# bandmodule.net
KiCad netlist of a schematic drawn in EAGLE
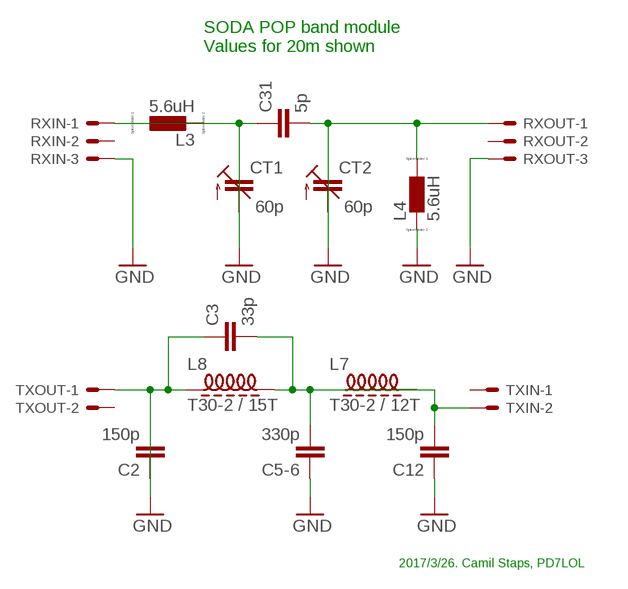
[diagram p0: schematic, sheet 1]

(export (version "E")
  (design (tool "Eeschema 10.0.6"))
  (components
    (comp (ref "C2")
      (value "150p")
      (footprint "eagle-import:C5B2.5")
      (libsource (lib "eagle-import") (part "C5/2.5"))
    )
    (comp (ref "C3")
      (value "33p")
      (footprint "eagle-import:C5B2.5")
      (libsource (lib "eagle-import") (part "C5/2.5"))
    )
    (comp (ref "C5-6")
      (value "330p")
      (footprint "eagle-import:C5B2.5")
      (libsource (lib "eagle-import") (part "C5/2.5"))
    )
    (comp (ref "C12")
      (value "150p")
      (footprint "eagle-import:C5B2.5")
      (libsource (lib "eagle-import") (part "C5/2.5"))
    )
    (comp (ref "C31")
      (value "5p")
      (footprint "eagle-import:C5B2.5")
      (libsource (lib "eagle-import") (part "C5/2.5"))
    )
    (comp (ref "CT1")
      (value "60p")
      (footprint "eagle-import:CTRIMTZ03")
      (libsource (lib "eagle-import") (part "C-TRIMMTZ03"))
    )
    (comp (ref "CT2")
      (value "60p")
      (footprint "eagle-import:CTRIMTZ03")
      (libsource (lib "eagle-import") (part "C-TRIMMTZ03"))
    )
    (comp (ref "L3")
      (value "5.6uH")
      (footprint "eagle-import:0207_10")
      (libsource (lib "eagle-import") (part "L0207/10"))
    )
    (comp (ref "L4")
      (value "5.6uH")
      (footprint "eagle-import:0207_10")
      (libsource (lib "eagle-import") (part "L0207/10"))
    )
    (comp (ref "L7")
      (value "T30-2 / 12T")
      (footprint "eagle-import:T30-2-28AWG-12T")
      (libsource (lib "eagle-import") (part "INDUCTORT30-2-28AWG-12T"))
    )
    (comp (ref "L8")
      (value "T30-2 / 15T")
      (footprint "eagle-import:T30-2-28AWG-12T")
      (libsource (lib "eagle-import") (part "INDUCTORT30-2-28AWG-12T"))
    )
    (comp (ref "RXIN")
      (value "22-23-2031")
      (footprint "eagle-import:22-23-2031")
      (fields (field (name "MF") "MOLEX"))
      (libsource (lib "eagle-import") (part "22-23-2031"))
    )
    (comp (ref "RXOUT")
      (value "22-23-2031")
      (footprint "eagle-import:22-23-2031")
      (fields (field (name "MF") "MOLEX"))
      (libsource (lib "eagle-import") (part "22-23-2031"))
    )
    (comp (ref "TXIN")
      (value "22-23-2021")
      (footprint "eagle-import:22-23-2021")
      (fields (field (name "MF") "MOLEX"))
      (libsource (lib "eagle-import") (part "22-23-2021"))
    )
    (comp (ref "TXOUT")
      (value "22-23-2021")
      (footprint "eagle-import:22-23-2021")
      (fields (field (name "MF") "MOLEX"))
      (libsource (lib "eagle-import") (part "22-23-2021"))
    )
  )
  (nets
    (net (code "1") (name "GND") (class "Default")
      (node (ref "C12") (pin "1") (pinfunction "1_1") (pintype "passive"))
      (node (ref "C2") (pin "2") (pinfunction "2_2") (pintype "passive"))
      (node (ref "C5-6") (pin "1") (pinfunction "1_1") (pintype "passive"))
      (node (ref "CT1") (pin "1") (pinfunction "E_1") (pintype "passive"))
      (node (ref "CT2") (pin "1") (pinfunction "E_1") (pintype "passive"))
      (node (ref "L4") (pin "2") (pinfunction "2_2") (pintype "passive"))
      (node (ref "RXIN") (pin "3") (pinfunction "S_3") (pintype "passive"))
      (node (ref "RXOUT") (pin "3") (pinfunction "S_3") (pintype "passive"))
    )
    (net (code "2") (name "Net-(CT1-A)") (class "Default")
      (node (ref "C31") (pin "1") (pinfunction "1_1") (pintype "passive"))
      (node (ref "CT1") (pin "2") (pinfunction "A_2") (pintype "passive"))
      (node (ref "L3") (pin "1") (pinfunction "1_1") (pintype "passive"))
    )
    (net (code "3") (name "Net-(CT2-A)") (class "Default")
      (node (ref "C31") (pin "2") (pinfunction "2_2") (pintype "passive"))
      (node (ref "CT2") (pin "2") (pinfunction "A_2") (pintype "passive"))
      (node (ref "L4") (pin "1") (pinfunction "1_1") (pintype "passive"))
      (node (ref "RXOUT") (pin "1") (pinfunction "S_1") (pintype "passive"))
    )
    (net (code "4") (name "Net-(L7-1)") (class "Default")
      (node (ref "C12") (pin "2") (pinfunction "2_2") (pintype "passive"))
      (node (ref "L7") (pin "P$1") (pinfunction "1_P$1") (pintype "passive"))
      (node (ref "TXIN") (pin "2") (pinfunction "S_2") (pintype "passive"))
    )
    (net (code "5") (name "Net-(L7-2)") (class "Default")
      (node (ref "C3") (pin "2") (pinfunction "2_2") (pintype "passive"))
      (node (ref "C5-6") (pin "2") (pinfunction "2_2") (pintype "passive"))
      (node (ref "L7") (pin "P$2") (pinfunction "2_P$2") (pintype "passive"))
      (node (ref "L8") (pin "P$2") (pinfunction "2_P$2") (pintype "passive"))
    )
    (net (code "6") (name "Net-(L8-1)") (class "Default")
      (node (ref "C2") (pin "1") (pinfunction "1_1") (pintype "passive"))
      (node (ref "C3") (pin "1") (pinfunction "1_1") (pintype "passive"))
      (node (ref "L8") (pin "P$1") (pinfunction "1_P$1") (pintype "passive"))
      (node (ref "TXOUT") (pin "1") (pinfunction "S_1") (pintype "passive"))
    )
    (net (code "7") (name "Net-(RXINA-S)") (class "Default")
      (node (ref "L3") (pin "2") (pinfunction "2_2") (pintype "passive"))
      (node (ref "RXIN") (pin "1") (pinfunction "S_1") (pintype "passive"))
    )
    (net (code "8") (name "unconnected-(RXINB-S-Pad2)") (class "Default")
      (node (ref "RXIN") (pin "2") (pinfunction "S_2") (pintype "passive"))
    )
    (net (code "9") (name "unconnected-(RXOUTB-S-Pad2)") (class "Default")
      (node (ref "RXOUT") (pin "2") (pinfunction "S_2") (pintype "passive"))
    )
    (net (code "10") (name "unconnected-(TXINA-S-Pad1)") (class "Default")
      (node (ref "TXIN") (pin "1") (pinfunction "S_1") (pintype "passive"))
    )
    (net (code "11") (name "unconnected-(TXOUTB-S-Pad2)") (class "Default")
      (node (ref "TXOUT") (pin "2") (pinfunction "S_2") (pintype "passive"))
    )
  )
)
